# FLEXQCMV1_3.net
KiCad netlist of a schematic drawn in EAGLE
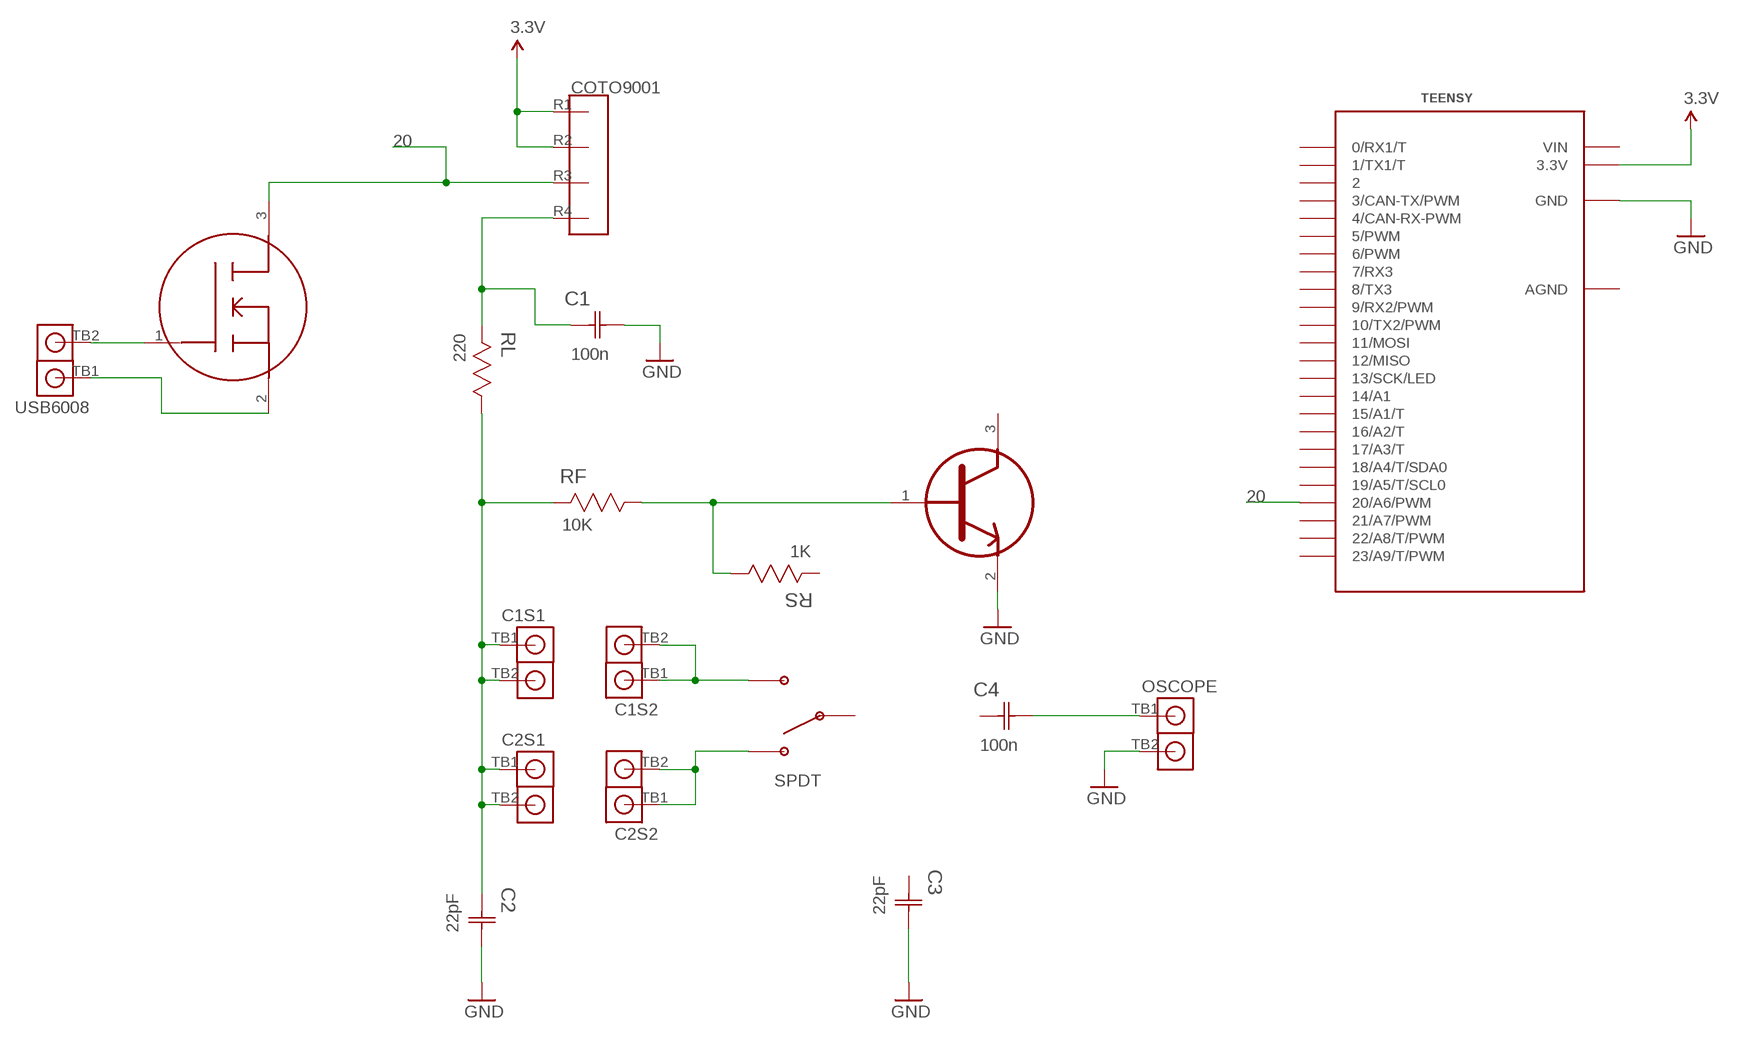
[diagram p0: schematic, sheet 1]

(export (version "E")
  (design (tool "Eeschema 10.0.6"))
  (components
    (comp (ref "C1")
      (value "100n")
      (footprint "eagle-import:CAPC3216X88N")
      (fields (field (name "MPN") "C1206C104K1RACTU") (field (name "TOLERANCE") "±10%"))
      (libsource (lib "eagle-import") (part "C1206C104K1RACTU"))
    )
    (comp (ref "C1S1")
      (value "TERMBLOCKX2")
      (footprint "eagle-import:TERMBLOCKX2")
      (libsource (lib "eagle-import") (part "TERMBLOCKX2"))
    )
    (comp (ref "C1S2")
      (value "TERMBLOCKX2")
      (footprint "eagle-import:TERMBLOCKX2")
      (libsource (lib "eagle-import") (part "TERMBLOCKX2"))
    )
    (comp (ref "C2")
      (value "22pF")
      (footprint "eagle-import:CAPC3216X88N")
      (fields (field (name "MPN") "C1206C220J5GACTU") (field (name "TOLERANCE") "±5%"))
      (libsource (lib "eagle-import") (part "C1206C220J5GACTU"))
    )
    (comp (ref "C2S1")
      (value "TERMBLOCKX2")
      (footprint "eagle-import:TERMBLOCKX2")
      (libsource (lib "eagle-import") (part "TERMBLOCKX2"))
    )
    (comp (ref "C2S2")
      (value "TERMBLOCKX2")
      (footprint "eagle-import:TERMBLOCKX2")
      (libsource (lib "eagle-import") (part "TERMBLOCKX2"))
    )
    (comp (ref "C3")
      (value "22pF")
      (footprint "eagle-import:CAPC3216X88N")
      (fields (field (name "MPN") "C1206C220J5GACTU") (field (name "TOLERANCE") "±5%"))
      (libsource (lib "eagle-import") (part "C1206C220J5GACTU"))
    )
    (comp (ref "C4")
      (value "100n")
      (footprint "eagle-import:CAPC3216X88N")
      (fields (field (name "MPN") "C1206C104K1RACTU") (field (name "TOLERANCE") "±10%"))
      (libsource (lib "eagle-import") (part "C1206C104K1RACTU"))
    )
    (comp (ref "COTO9001")
      (value "COTO9001")
      (footprint "eagle-import:COTO9001")
      (libsource (lib "eagle-import") (part "COTO9001"))
    )
    (comp (ref "OSCOPE")
      (value "TERMBLOCKX2")
      (footprint "eagle-import:TERMBLOCKX2")
      (libsource (lib "eagle-import") (part "TERMBLOCKX2"))
    )
    (comp (ref "RF")
      (value "10K")
      (footprint "eagle-import:RESC3216X71N")
      (fields (field (name "MPN") "CRCW120610K0FKEA") (field (name "TOLERANCE") "±1%"))
      (libsource (lib "eagle-import") (part "CRCW120610K0FKEA"))
    )
    (comp (ref "RL")
      (value "220")
      (footprint "eagle-import:RESC3216X71N")
      (fields (field (name "MPN") "CRCW1206220RJNEA") (field (name "TOLERANCE") "±5%"))
      (libsource (lib "eagle-import") (part "CRCW1206220RJNEA"))
    )
    (comp (ref "RS")
      (value "1K")
      (footprint "eagle-import:RESC3216X71N")
      (fields (field (name "MPN") "CRCW12061K00FKEA") (field (name "TOLERANCE") "±1%"))
      (libsource (lib "eagle-import") (part "CRCW12061K00FKEA"))
    )
    (comp (ref "SPDT")
      (value "SPDTSWITCH")
      (footprint "eagle-import:SPDTSWITCH")
      (libsource (lib "eagle-import") (part "SPDTSWITCH"))
    )
    (comp (ref "TEENSY")
      (value "TEENSY_3.1_DIL")
      (footprint "eagle-import:TEENSY3-DIL")
      (libsource (lib "eagle-import") (part "TEENSY_3.1_DIL"))
    )
    (comp (ref "U1")
      (value "FET")
      (footprint "eagle-import:SOT95P230X110-3N")
      (fields (field (name "MPN") "2N7002K"))
      (libsource (lib "eagle-import") (part "2N7002K"))
    )
    (comp (ref "U2")
      (value "BJT")
      (footprint "eagle-import:SOT95P230X110-3N")
      (libsource (lib "eagle-import") (part "BC847C"))
    )
    (comp (ref "USB6008")
      (value "TERMBLOCKX2")
      (footprint "eagle-import:TERMBLOCKX2")
      (libsource (lib "eagle-import") (part "TERMBLOCKX2"))
    )
  )
  (nets
    (net (code "1") (name "/20") (class "Default")
      (node (ref "COTO9001") (pin "R3") (pinfunction "R3_R3") (pintype "bidirectional"))
      (node (ref "TEENSY") (pin "20/A6") (pinfunction "20/A6/PWM_20/A6") (pintype "bidirectional"))
      (node (ref "U1") (pin "3") (pinfunction "D_3") (pintype "bidirectional"))
    )
    (net (code "2") (name "/AGND") (class "Default")
      (node (ref "TEENSY") (pin "AGND") (pinfunction "AGND_AGND") (pintype "power_in"))
    )
    (net (code "3") (name "/VIN") (class "Default")
      (node (ref "TEENSY") (pin "VIN") (pinfunction "VIN_VIN") (pintype "power_in"))
    )
    (net (code "4") (name "3.3V") (class "Default")
      (node (ref "COTO9001") (pin "R1") (pinfunction "R1_R1") (pintype "bidirectional"))
      (node (ref "COTO9001") (pin "R2") (pinfunction "R2_R2") (pintype "bidirectional"))
      (node (ref "TEENSY") (pin "3.3V") (pinfunction "3.3V_3.3V") (pintype "power_in"))
    )
    (net (code "5") (name "GND") (class "Default")
      (node (ref "C1") (pin "2") (pinfunction "C2_2") (pintype "passive"))
      (node (ref "C2") (pin "2") (pinfunction "C2_2") (pintype "passive"))
      (node (ref "C3") (pin "2") (pinfunction "C2_2") (pintype "passive"))
      (node (ref "OSCOPE") (pin "TB2") (pinfunction "TB2_TB2") (pintype "bidirectional"))
      (node (ref "TEENSY") (pin "GND") (pinfunction "GND_GND") (pintype "power_in"))
      (node (ref "U2") (pin "2") (pinfunction "E_2") (pintype "bidirectional"))
    )
    (net (code "6") (name "Net-(C1-C1)") (class "Default")
      (node (ref "C1") (pin "1") (pinfunction "C1_1") (pintype "passive"))
      (node (ref "COTO9001") (pin "R4") (pinfunction "R4_R4") (pintype "bidirectional"))
      (node (ref "RL") (pin "2") (pinfunction "2_2") (pintype "passive"))
    )
    (net (code "7") (name "Net-(C1S2-PadTB1)") (class "Default")
      (node (ref "C1S2") (pin "TB1") (pinfunction "TB1_TB1") (pintype "bidirectional"))
      (node (ref "C1S2") (pin "TB2") (pinfunction "TB2_TB2") (pintype "bidirectional"))
      (node (ref "SPDT") (pin "SW3") (pinfunction "SW3_SW3") (pintype "bidirectional"))
    )
    (net (code "8") (name "Net-(C2-C1)") (class "Default")
      (node (ref "C1S1") (pin "TB1") (pinfunction "TB1_TB1") (pintype "bidirectional"))
      (node (ref "C1S1") (pin "TB2") (pinfunction "TB2_TB2") (pintype "bidirectional"))
      (node (ref "C2") (pin "1") (pinfunction "C1_1") (pintype "passive"))
      (node (ref "C2S1") (pin "TB1") (pinfunction "TB1_TB1") (pintype "bidirectional"))
      (node (ref "C2S1") (pin "TB2") (pinfunction "TB2_TB2") (pintype "bidirectional"))
      (node (ref "RF") (pin "2") (pinfunction "2_2") (pintype "passive"))
      (node (ref "RL") (pin "1") (pinfunction "1_1") (pintype "passive"))
    )
    (net (code "9") (name "Net-(C2S2-PadTB1)") (class "Default")
      (node (ref "C2S2") (pin "TB1") (pinfunction "TB1_TB1") (pintype "bidirectional"))
      (node (ref "C2S2") (pin "TB2") (pinfunction "TB2_TB2") (pintype "bidirectional"))
      (node (ref "SPDT") (pin "SW1") (pinfunction "SW1_SW1") (pintype "bidirectional"))
    )
    (net (code "10") (name "Net-(C4-C2)") (class "Default")
      (node (ref "C4") (pin "2") (pinfunction "C2_2") (pintype "passive"))
      (node (ref "OSCOPE") (pin "TB1") (pinfunction "TB1_TB1") (pintype "bidirectional"))
    )
    (net (code "11") (name "Net-(U1-G)") (class "Default")
      (node (ref "U1") (pin "1") (pinfunction "G_1") (pintype "bidirectional"))
      (node (ref "USB6008") (pin "TB2") (pinfunction "TB2_TB2") (pintype "bidirectional"))
    )
    (net (code "12") (name "Net-(U1-S)") (class "Default")
      (node (ref "U1") (pin "2") (pinfunction "S_2") (pintype "bidirectional"))
      (node (ref "USB6008") (pin "TB1") (pinfunction "TB1_TB1") (pintype "bidirectional"))
    )
    (net (code "13") (name "Net-(U2-B)") (class "Default")
      (node (ref "RF") (pin "1") (pinfunction "1_1") (pintype "passive"))
      (node (ref "RS") (pin "1") (pinfunction "1_1") (pintype "passive"))
      (node (ref "U2") (pin "1") (pinfunction "B_1") (pintype "bidirectional"))
    )
    (net (code "14") (name "unconnected-(C3-C1-Pad1)") (class "Default")
      (node (ref "C3") (pin "1") (pinfunction "C1_1") (pintype "passive"))
    )
    (net (code "15") (name "unconnected-(C4-C1-Pad1)") (class "Default")
      (node (ref "C4") (pin "1") (pinfunction "C1_1") (pintype "passive"))
    )
    (net (code "16") (name "unconnected-(RS-Pad2)") (class "Default")
      (node (ref "RS") (pin "2") (pinfunction "2_2") (pintype "passive"))
    )
    (net (code "17") (name "unconnected-(SPDT-PadSW2)") (class "Default")
      (node (ref "SPDT") (pin "SW2") (pinfunction "SW2_SW2") (pintype "bidirectional"))
    )
    (net (code "18") (name "unconnected-(TEENSY-0{slash}RX1{slash}T-Pad0)") (class "Default")
      (node (ref "TEENSY") (pin "0") (pinfunction "0/RX1/T_0") (pintype "bidirectional"))
    )
    (net (code "19") (name "unconnected-(TEENSY-1{slash}TX1{slash}T-Pad1)") (class "Default")
      (node (ref "TEENSY") (pin "1") (pinfunction "1/TX1/T_1") (pintype "bidirectional"))
    )
    (net (code "20") (name "unconnected-(TEENSY-3{slash}CAN-TX{slash}PWM-Pad3)") (class "Default")
      (node (ref "TEENSY") (pin "3") (pinfunction "3/CAN-TX/PWM_3") (pintype "bidirectional"))
    )
    (net (code "21") (name "unconnected-(TEENSY-4{slash}CAN-RX-PWM-Pad4)") (class "Default")
      (node (ref "TEENSY") (pin "4") (pinfunction "4/CAN-RX-PWM_4") (pintype "bidirectional"))
    )
    (net (code "22") (name "unconnected-(TEENSY-5{slash}PWM-Pad5)") (class "Default")
      (node (ref "TEENSY") (pin "5") (pinfunction "5/PWM_5") (pintype "bidirectional"))
    )
    (net (code "23") (name "unconnected-(TEENSY-6{slash}PWM-Pad6)") (class "Default")
      (node (ref "TEENSY") (pin "6") (pinfunction "6/PWM_6") (pintype "bidirectional"))
    )
    (net (code "24") (name "unconnected-(TEENSY-7{slash}RX3-Pad7)") (class "Default")
      (node (ref "TEENSY") (pin "7") (pinfunction "7/RX3_7") (pintype "bidirectional"))
    )
    (net (code "25") (name "unconnected-(TEENSY-8{slash}TX3-Pad8)") (class "Default")
      (node (ref "TEENSY") (pin "8") (pinfunction "8/TX3_8") (pintype "bidirectional"))
    )
    (net (code "26") (name "unconnected-(TEENSY-9{slash}RX2{slash}PWM-Pad9)") (class "Default")
      (node (ref "TEENSY") (pin "9") (pinfunction "9/RX2/PWM_9") (pintype "bidirectional"))
    )
    (net (code "27") (name "unconnected-(TEENSY-10{slash}TX2{slash}PWM-Pad10)") (class "Default")
      (node (ref "TEENSY") (pin "10") (pinfunction "10/TX2/PWM_10") (pintype "bidirectional"))
    )
    (net (code "28") (name "unconnected-(TEENSY-11{slash}MOSI-Pad11)") (class "Default")
      (node (ref "TEENSY") (pin "11") (pinfunction "11/MOSI_11") (pintype "bidirectional"))
    )
    (net (code "29") (name "unconnected-(TEENSY-12{slash}MISO-Pad12)") (class "Default")
      (node (ref "TEENSY") (pin "12") (pinfunction "12/MISO_12") (pintype "bidirectional"))
    )
    (net (code "30") (name "unconnected-(TEENSY-13{slash}SCK{slash}LED-Pad13)") (class "Default")
      (node (ref "TEENSY") (pin "13") (pinfunction "13/SCK/LED_13") (pintype "bidirectional"))
    )
    (net (code "31") (name "unconnected-(TEENSY-14{slash}A1-Pad14{slash}A0)") (class "Default")
      (node (ref "TEENSY") (pin "14/A0") (pinfunction "14/A1_14/A0") (pintype "bidirectional"))
    )
    (net (code "32") (name "unconnected-(TEENSY-15{slash}A1{slash}T-Pad15{slash}A1)") (class "Default")
      (node (ref "TEENSY") (pin "15/A1") (pinfunction "15/A1/T_15/A1") (pintype "bidirectional"))
    )
    (net (code "33") (name "unconnected-(TEENSY-16{slash}A2{slash}T-Pad16{slash}A2)") (class "Default")
      (node (ref "TEENSY") (pin "16/A2") (pinfunction "16/A2/T_16/A2") (pintype "bidirectional"))
    )
    (net (code "34") (name "unconnected-(TEENSY-17{slash}A3{slash}T-Pad17{slash}A3)") (class "Default")
      (node (ref "TEENSY") (pin "17/A3") (pinfunction "17/A3/T_17/A3") (pintype "bidirectional"))
    )
    (net (code "35") (name "unconnected-(TEENSY-18{slash}A4{slash}T{slash}SDA0-Pad18{slash}A4)") (class "Default")
      (node (ref "TEENSY") (pin "18/A4") (pinfunction "18/A4/T/SDA0_18/A4") (pintype "bidirectional"))
    )
    (net (code "36") (name "unconnected-(TEENSY-19{slash}A5{slash}T{slash}SCL0-Pad19{slash}A5)") (class "Default")
      (node (ref "TEENSY") (pin "19/A5") (pinfunction "19/A5/T/SCL0_19/A5") (pintype "bidirectional"))
    )
    (net (code "37") (name "unconnected-(TEENSY-21{slash}A7{slash}PWM-Pad21{slash}A7)") (class "Default")
      (node (ref "TEENSY") (pin "21/A7") (pinfunction "21/A7/PWM_21/A7") (pintype "bidirectional"))
    )
    (net (code "38") (name "unconnected-(TEENSY-22{slash}A8{slash}T{slash}PWM-Pad22{slash}A8)") (class "Default")
      (node (ref "TEENSY") (pin "22/A8") (pinfunction "22/A8/T/PWM_22/A8") (pintype "bidirectional"))
    )
    (net (code "39") (name "unconnected-(TEENSY-23{slash}A9{slash}T{slash}PWM-Pad23{slash}A9)") (class "Default")
      (node (ref "TEENSY") (pin "23/A9") (pinfunction "23/A9/T/PWM_23/A9") (pintype "bidirectional"))
    )
    (net (code "40") (name "unconnected-(TEENSY-Pad2)") (class "Default")
      (node (ref "TEENSY") (pin "2") (pinfunction "2_2") (pintype "bidirectional"))
    )
    (net (code "41") (name "unconnected-(U2-C-Pad3)") (class "Default")
      (node (ref "U2") (pin "3") (pinfunction "C_3") (pintype "bidirectional"))
    )
  )
)
